# SNES-logo-leds.net
KiCad netlist of a schematic drawn in EAGLE
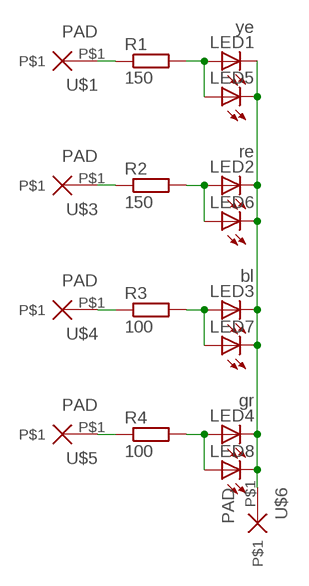
[diagram p0: schematic, sheet 1]

(export (version "E")
  (design (tool "Eeschema 10.0.6"))
  (components
    (comp (ref "LED1")
      (value "ye")
      (footprint "eagle-import:SML0805")
      (libsource (lib "eagle-import") (part "LEDSML0805"))
    )
    (comp (ref "LED2")
      (value "re")
      (footprint "eagle-import:SML0805")
      (libsource (lib "eagle-import") (part "LEDSML0805"))
    )
    (comp (ref "LED3")
      (value "bl")
      (footprint "eagle-import:SML0805")
      (libsource (lib "eagle-import") (part "LEDSML0805"))
    )
    (comp (ref "LED4")
      (value "gr")
      (footprint "eagle-import:SML0805")
      (libsource (lib "eagle-import") (part "LEDSML0805"))
    )
    (comp (ref "LED5")
      (value "LEDP-LCC-2")
      (footprint "eagle-import:P-LCC-2")
      (libsource (lib "eagle-import") (part "LEDP-LCC-2"))
    )
    (comp (ref "LED6")
      (value "LEDP-LCC-2")
      (footprint "eagle-import:P-LCC-2")
      (libsource (lib "eagle-import") (part "LEDP-LCC-2"))
    )
    (comp (ref "LED7")
      (value "LEDP-LCC-2")
      (footprint "eagle-import:P-LCC-2")
      (libsource (lib "eagle-import") (part "LEDP-LCC-2"))
    )
    (comp (ref "LED8")
      (value "LEDP-LCC-2")
      (footprint "eagle-import:P-LCC-2")
      (libsource (lib "eagle-import") (part "LEDP-LCC-2"))
    )
    (comp (ref "R1")
      (value "150")
      (footprint "eagle-import:Z0805")
      (libsource (lib "eagle-import") (part "R0805"))
    )
    (comp (ref "R2")
      (value "150")
      (footprint "eagle-import:Z0805")
      (libsource (lib "eagle-import") (part "R0805"))
    )
    (comp (ref "R3")
      (value "100")
      (footprint "eagle-import:Z0805")
      (libsource (lib "eagle-import") (part "R0805"))
    )
    (comp (ref "R4")
      (value "100")
      (footprint "eagle-import:Z0805")
      (libsource (lib "eagle-import") (part "R0805"))
    )
    (comp (ref "U$1")
      (value "PAD")
      (footprint "eagle-import:PAD")
      (libsource (lib "eagle-import") (part "PAD"))
    )
    (comp (ref "U$3")
      (value "PAD")
      (footprint "eagle-import:PAD")
      (libsource (lib "eagle-import") (part "PAD"))
    )
    (comp (ref "U$4")
      (value "PAD")
      (footprint "eagle-import:PAD")
      (libsource (lib "eagle-import") (part "PAD"))
    )
    (comp (ref "U$5")
      (value "PAD")
      (footprint "eagle-import:PAD")
      (libsource (lib "eagle-import") (part "PAD"))
    )
    (comp (ref "U$6")
      (value "PAD")
      (footprint "eagle-import:PAD")
      (libsource (lib "eagle-import") (part "PAD"))
    )
  )
  (nets
    (net (code "1") (name "Net-(LED1-PadA)") (class "Default")
      (node (ref "LED1") (pin "A") (pinfunction "A_A") (pintype "passive"))
      (node (ref "LED5") (pin "A") (pinfunction "A_A") (pintype "passive"))
      (node (ref "R1") (pin "2") (pinfunction "2_2") (pintype "passive"))
    )
    (net (code "2") (name "Net-(LED1-PadC)") (class "Default")
      (node (ref "LED1") (pin "C") (pinfunction "C_C") (pintype "passive"))
      (node (ref "LED2") (pin "C") (pinfunction "C_C") (pintype "passive"))
      (node (ref "LED3") (pin "C") (pinfunction "C_C") (pintype "passive"))
      (node (ref "LED4") (pin "C") (pinfunction "C_C") (pintype "passive"))
      (node (ref "LED5") (pin "C") (pinfunction "C_C") (pintype "passive"))
      (node (ref "LED6") (pin "C") (pinfunction "C_C") (pintype "passive"))
      (node (ref "LED7") (pin "C") (pinfunction "C_C") (pintype "passive"))
      (node (ref "LED8") (pin "C") (pinfunction "C_C") (pintype "passive"))
      (node (ref "U$6") (pin "P$1") (pinfunction "P$1_P$1") (pintype "bidirectional"))
    )
    (net (code "3") (name "Net-(LED2-PadA)") (class "Default")
      (node (ref "LED2") (pin "A") (pinfunction "A_A") (pintype "passive"))
      (node (ref "LED6") (pin "A") (pinfunction "A_A") (pintype "passive"))
      (node (ref "R2") (pin "2") (pinfunction "2_2") (pintype "passive"))
    )
    (net (code "4") (name "Net-(LED3-PadA)") (class "Default")
      (node (ref "LED3") (pin "A") (pinfunction "A_A") (pintype "passive"))
      (node (ref "LED7") (pin "A") (pinfunction "A_A") (pintype "passive"))
      (node (ref "R3") (pin "2") (pinfunction "2_2") (pintype "passive"))
    )
    (net (code "5") (name "Net-(LED4-PadA)") (class "Default")
      (node (ref "LED4") (pin "A") (pinfunction "A_A") (pintype "passive"))
      (node (ref "LED8") (pin "A") (pinfunction "A_A") (pintype "passive"))
      (node (ref "R4") (pin "2") (pinfunction "2_2") (pintype "passive"))
    )
    (net (code "6") (name "Net-(R1-Pad1)") (class "Default")
      (node (ref "R1") (pin "1") (pinfunction "1_1") (pintype "passive"))
      (node (ref "U$1") (pin "P$1") (pinfunction "P$1_P$1") (pintype "bidirectional"))
    )
    (net (code "7") (name "Net-(R2-Pad1)") (class "Default")
      (node (ref "R2") (pin "1") (pinfunction "1_1") (pintype "passive"))
      (node (ref "U$3") (pin "P$1") (pinfunction "P$1_P$1") (pintype "bidirectional"))
    )
    (net (code "8") (name "Net-(R3-Pad1)") (class "Default")
      (node (ref "R3") (pin "1") (pinfunction "1_1") (pintype "passive"))
      (node (ref "U$4") (pin "P$1") (pinfunction "P$1_P$1") (pintype "bidirectional"))
    )
    (net (code "9") (name "Net-(R4-Pad1)") (class "Default")
      (node (ref "R4") (pin "1") (pinfunction "1_1") (pintype "passive"))
      (node (ref "U$5") (pin "P$1") (pinfunction "P$1_P$1") (pintype "bidirectional"))
    )
  )
)
